# Sheet1.net
KiCad netlist of a schematic drawn in Altium Designer
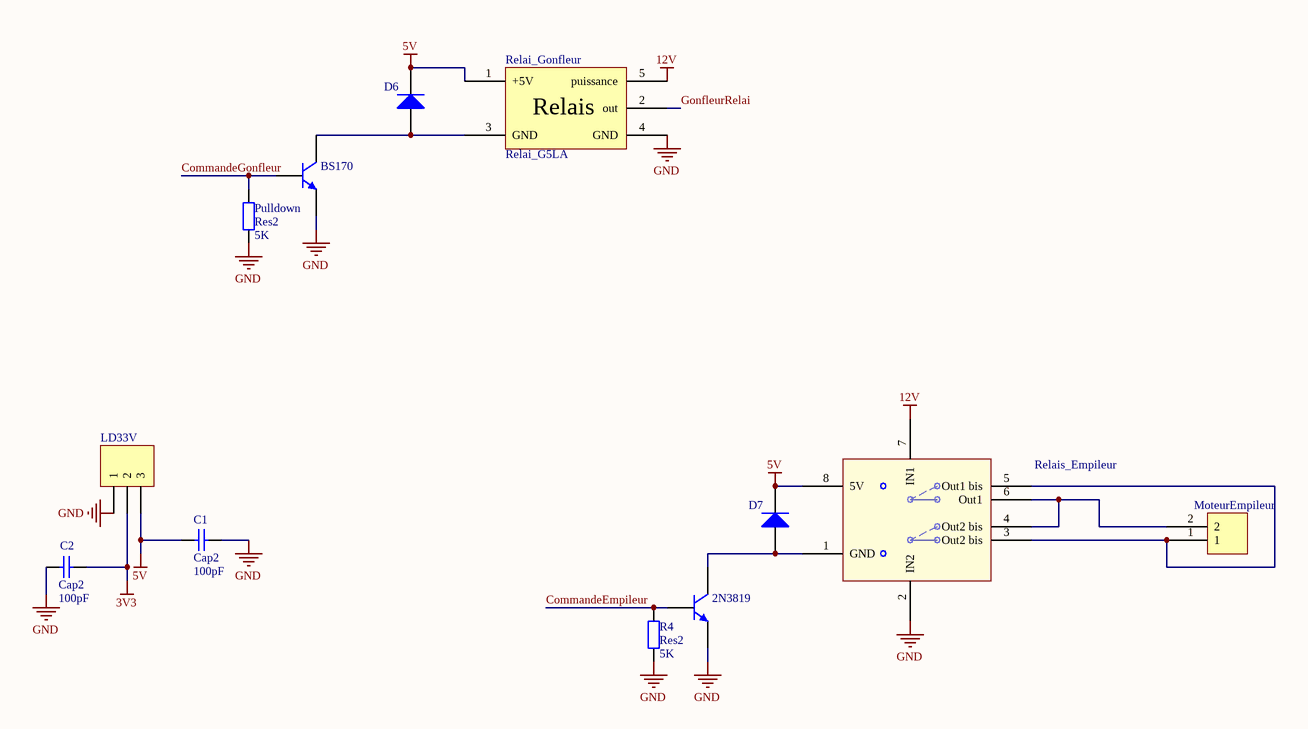
[diagram p0: Sheet1.SchDoc]

(export (version "E")
  (design (tool "Eeschema 10.0.6"))
  (components
    (comp (ref "2N3819")
      (value "2N3904")
      (footprint "TO92")
      (description "NPN General Purpose Amplifier")
      (fields (field (name "PUBLISHER") "Altium Limited"))
      (libsource (lib "LIBRAIRIE_INTEGREE_PHELMA1") (part "2N3904"))
    )
    (comp (ref "BS170")
      (value "2N3904")
      (footprint "TO92")
      (description "NPN General Purpose Amplifier")
      (fields (field (name "PUBLISHER") "Altium Limited"))
      (libsource (lib "LIBRAIRIE_INTEGREE_PHELMA1") (part "2N3904"))
    )
    (comp (ref "C1")
      (value "Cap2")
      (footprint "CAPA2")
      (description "Capacitor")
      (fields (field (name "ALTIUM_VALUE") "100pF") (field (name "PUBLISHER") "Altium Limited"))
      (libsource (lib "LIBRAIRIE_INTEGREE_PHELMA1") (part "Cap2"))
    )
    (comp (ref "C2")
      (value "Cap2")
      (footprint "CAPA2")
      (description "Capacitor")
      (fields (field (name "ALTIUM_VALUE") "100pF") (field (name "PUBLISHER") "Altium Limited"))
      (libsource (lib "LIBRAIRIE_INTEGREE_PHELMA1") (part "Cap2"))
    )
    (comp (ref "D6")
      (value "Diode 1N4001")
      (footprint "Ddiode")
      (description "1 Amp General Purpose Rectifier")
      (fields (field (name "PUBLISHER") "Altium Limited"))
      (libsource (lib "LIBRAIRIE_INTEGREE_PHELMA1") (part "Diode 1N4001"))
    )
    (comp (ref "D7")
      (value "Diode 1N4001")
      (footprint "Ddiode")
      (description "1 Amp General Purpose Rectifier")
      (fields (field (name "PUBLISHER") "Altium Limited"))
      (libsource (lib "LIBRAIRIE_INTEGREE_PHELMA1") (part "Diode 1N4001"))
    )
    (comp (ref "LD33V")
      (value "Header 3")
      (footprint "HDR1X3")
      (description "Header, 3-Pin")
      (fields (field (name "PUBLISHER") "Altium Limited"))
      (libsource (lib "Miscellaneous Connectors") (part "Header 3"))
    )
    (comp (ref "MoteurEmpileur")
      (value "Bornier")
      (footprint "Bornier")
      (libsource (lib "lib_Robotronik") (part "Bornier2"))
    )
    (comp (ref "Pulldown")
      (value "Res2")
      (footprint "res5_1/4W")
      (description "Resistor")
      (fields (field (name "ALTIUM_VALUE") "5K") (field (name "PUBLISHER") "Altium Limited"))
      (libsource (lib "LIBRAIRIE_INTEGREE_PHELMA1") (part "Res2"))
    )
    (comp (ref "R4")
      (value "Res2")
      (footprint "res5_1/4W")
      (description "Resistor")
      (fields (field (name "ALTIUM_VALUE") "5K") (field (name "PUBLISHER") "Altium Limited"))
      (libsource (lib "LIBRAIRIE_INTEGREE_PHELMA1") (part "Res2"))
    )
    (comp (ref "Relais_Empileur")
      (value "Relais_MT2C93401")
      (footprint "Relais_MT2C93401")
      (libsource (lib "lib_Robotronik") (part "Relais_MT2C93401"))
    )
    (comp (ref "Relai_Gonfleur")
      (value "Relai_G5LA")
      (footprint "Relai_g5la-1")
      (libsource (lib "lib_Robotronik") (part "Relai_G5LA"))
    )
  )
  (nets
    (net (code "1") (name "/CommandeEmpileur") (class "Default")
      (node (ref "2N3819") (pin "2") (pinfunction "B_2") (pintype "passive"))
      (node (ref "R4") (pin "2") (pinfunction "2_2") (pintype "passive"))
    )
    (net (code "2") (name "/CommandeGonfleur") (class "Default")
      (node (ref "BS170") (pin "2") (pinfunction "B_2") (pintype "passive"))
      (node (ref "Pulldown") (pin "2") (pinfunction "2_2") (pintype "passive"))
    )
    (net (code "3") (name "/GonfleurRelai") (class "Default")
      (node (ref "Relai_Gonfleur") (pin "2") (pinfunction "out_2") (pintype "passive"))
    )
    (net (code "4") (name "3V3") (class "Default")
      (node (ref "C2") (pin "2") (pinfunction "2_2") (pintype "passive"))
      (node (ref "LD33V") (pin "2") (pinfunction "2_2") (pintype "passive"))
    )
    (net (code "5") (name "5V") (class "Default")
      (node (ref "C1") (pin "2") (pinfunction "2_2") (pintype "passive"))
      (node (ref "D6") (pin "2") (pinfunction "K_2") (pintype "passive"))
      (node (ref "D7") (pin "2") (pinfunction "K_2") (pintype "passive"))
      (node (ref "LD33V") (pin "3") (pinfunction "3_3") (pintype "passive"))
      (node (ref "Relai_Gonfleur") (pin "1") (pinfunction "+5V_1") (pintype "passive"))
      (node (ref "Relais_Empileur") (pin "8") (pinfunction "5V_8") (pintype "passive"))
    )
    (net (code "6") (name "12V") (class "Default")
      (node (ref "Relai_Gonfleur") (pin "5") (pinfunction "puissance_5") (pintype "passive"))
      (node (ref "Relais_Empileur") (pin "7") (pinfunction "IN1_7") (pintype "passive"))
    )
    (net (code "7") (name "GND") (class "Default")
      (node (ref "2N3819") (pin "1") (pinfunction "E_1") (pintype "passive"))
      (node (ref "BS170") (pin "1") (pinfunction "E_1") (pintype "passive"))
      (node (ref "C1") (pin "1") (pinfunction "1_1") (pintype "passive"))
      (node (ref "C2") (pin "1") (pinfunction "1_1") (pintype "passive"))
      (node (ref "LD33V") (pin "1") (pinfunction "1_1") (pintype "passive"))
      (node (ref "Pulldown") (pin "1") (pinfunction "1_1") (pintype "passive"))
      (node (ref "R4") (pin "1") (pinfunction "1_1") (pintype "passive"))
      (node (ref "Relai_Gonfleur") (pin "4") (pinfunction "GND_4") (pintype "passive"))
      (node (ref "Relais_Empileur") (pin "2") (pinfunction "IN2_2") (pintype "passive"))
    )
    (net (code "8") (name "Net-(2N3819-C)") (class "Default")
      (node (ref "2N3819") (pin "3") (pinfunction "C_3") (pintype "passive"))
      (node (ref "D7") (pin "1") (pinfunction "A_1") (pintype "passive"))
      (node (ref "Relais_Empileur") (pin "1") (pinfunction "GND_1") (pintype "passive"))
    )
    (net (code "9") (name "Net-(BS170-C)") (class "Default")
      (node (ref "BS170") (pin "3") (pinfunction "C_3") (pintype "passive"))
      (node (ref "D6") (pin "1") (pinfunction "A_1") (pintype "passive"))
      (node (ref "Relai_Gonfleur") (pin "3") (pinfunction "GND_3") (pintype "passive"))
    )
    (net (code "10") (name "Net-(Relais_Empileur-Out1)") (class "Default")
      (node (ref "MoteurEmpileur") (pin "2") (pinfunction "2_2") (pintype "passive"))
      (node (ref "Relais_Empileur") (pin "4") (pinfunction "Out2_bis_4") (pintype "passive"))
      (node (ref "Relais_Empileur") (pin "6") (pinfunction "Out1_6") (pintype "passive"))
    )
    (net (code "11") (name "Net-(Relais_Empileur-Out1_bis)") (class "Default")
      (node (ref "MoteurEmpileur") (pin "1") (pinfunction "1_1") (pintype "passive"))
      (node (ref "Relais_Empileur") (pin "3") (pinfunction "Out2_bis_3") (pintype "passive"))
      (node (ref "Relais_Empileur") (pin "5") (pinfunction "Out1_bis_5") (pintype "passive"))
    )
  )
)
